# EEZ_DIB_AUX_PS_r3B5.net
KiCad netlist of a schematic drawn in EAGLE
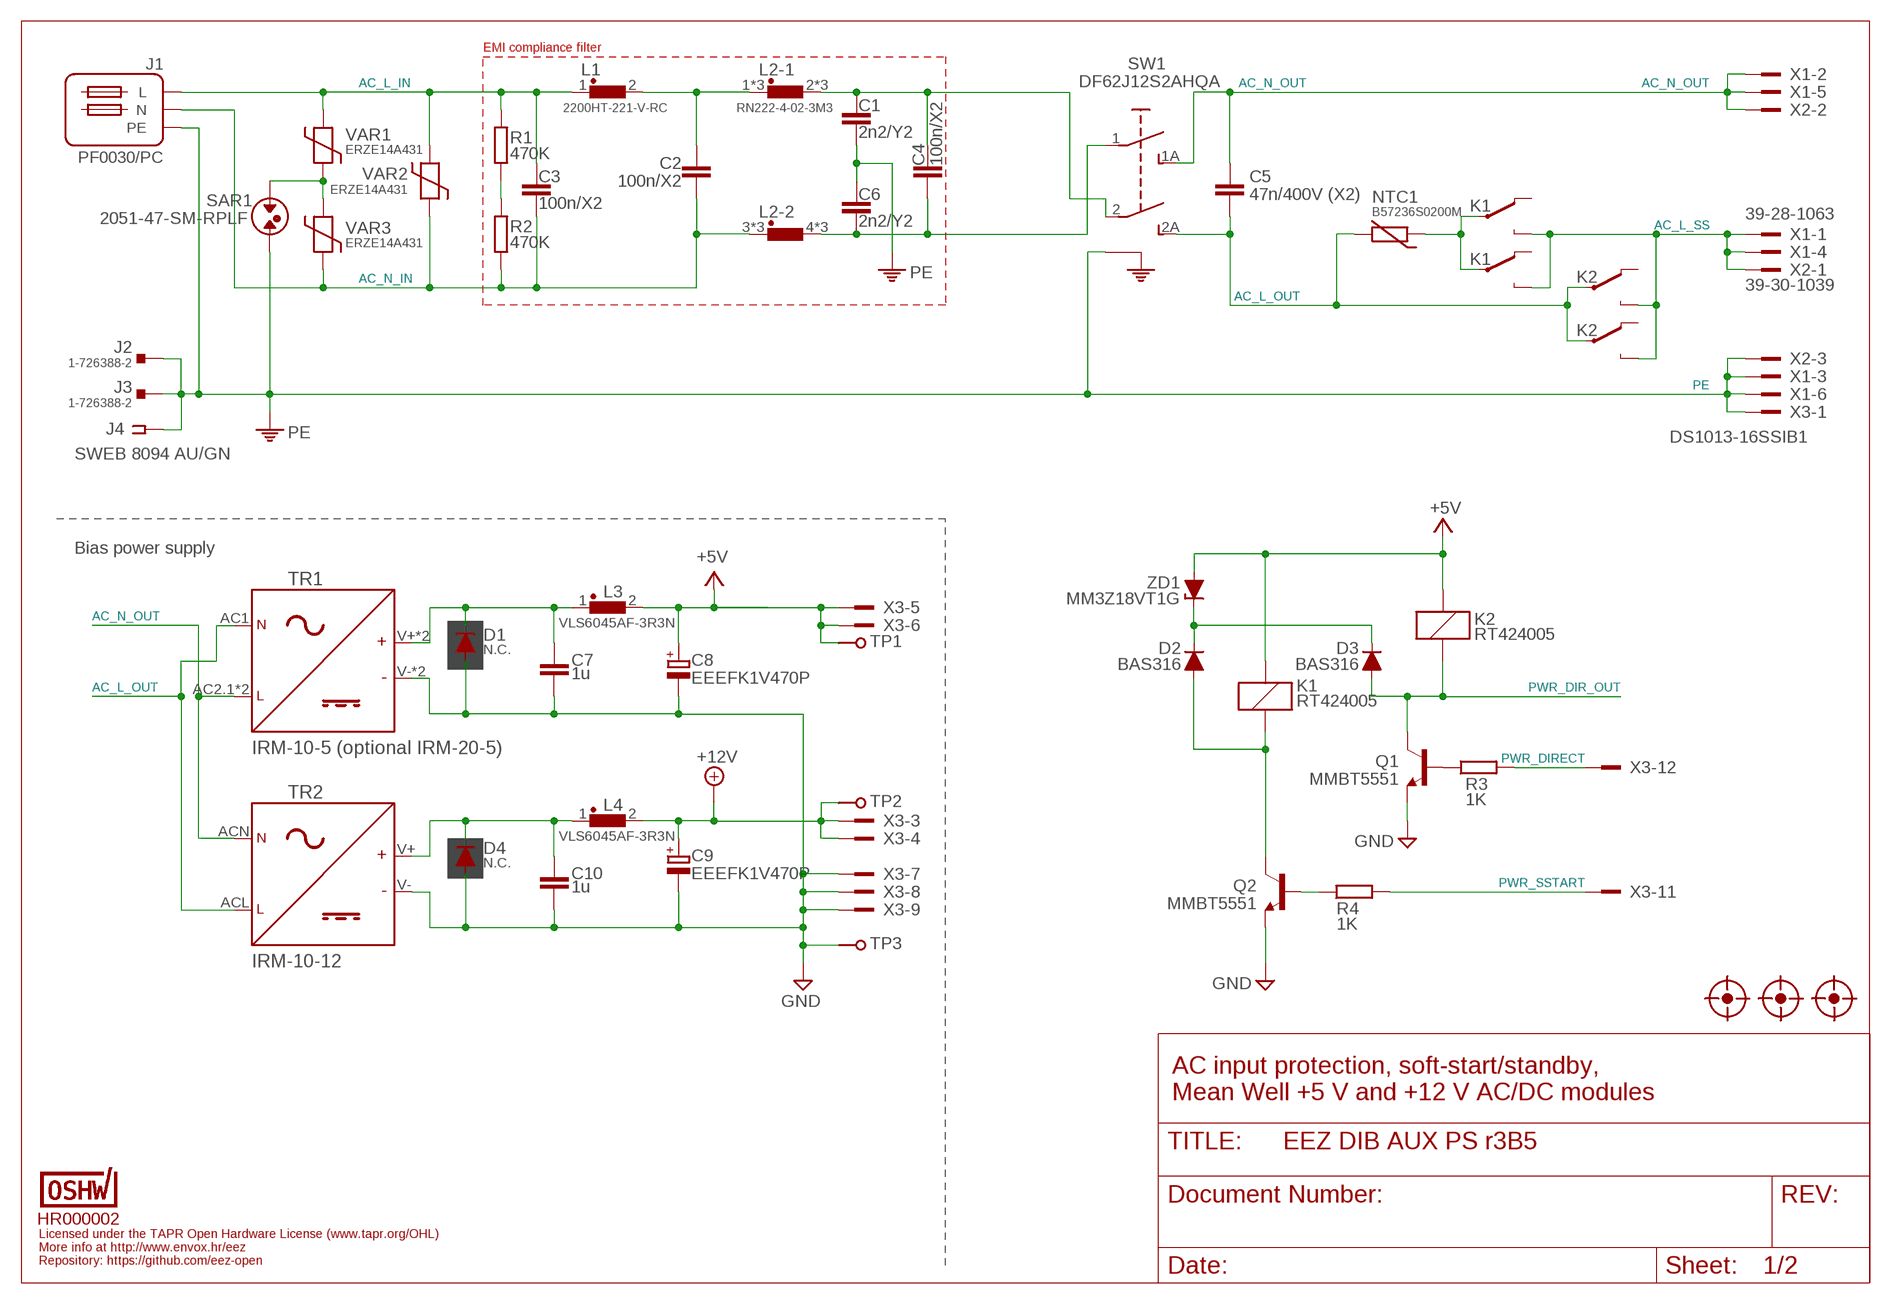
[diagram p0: schematic, sheet 1]
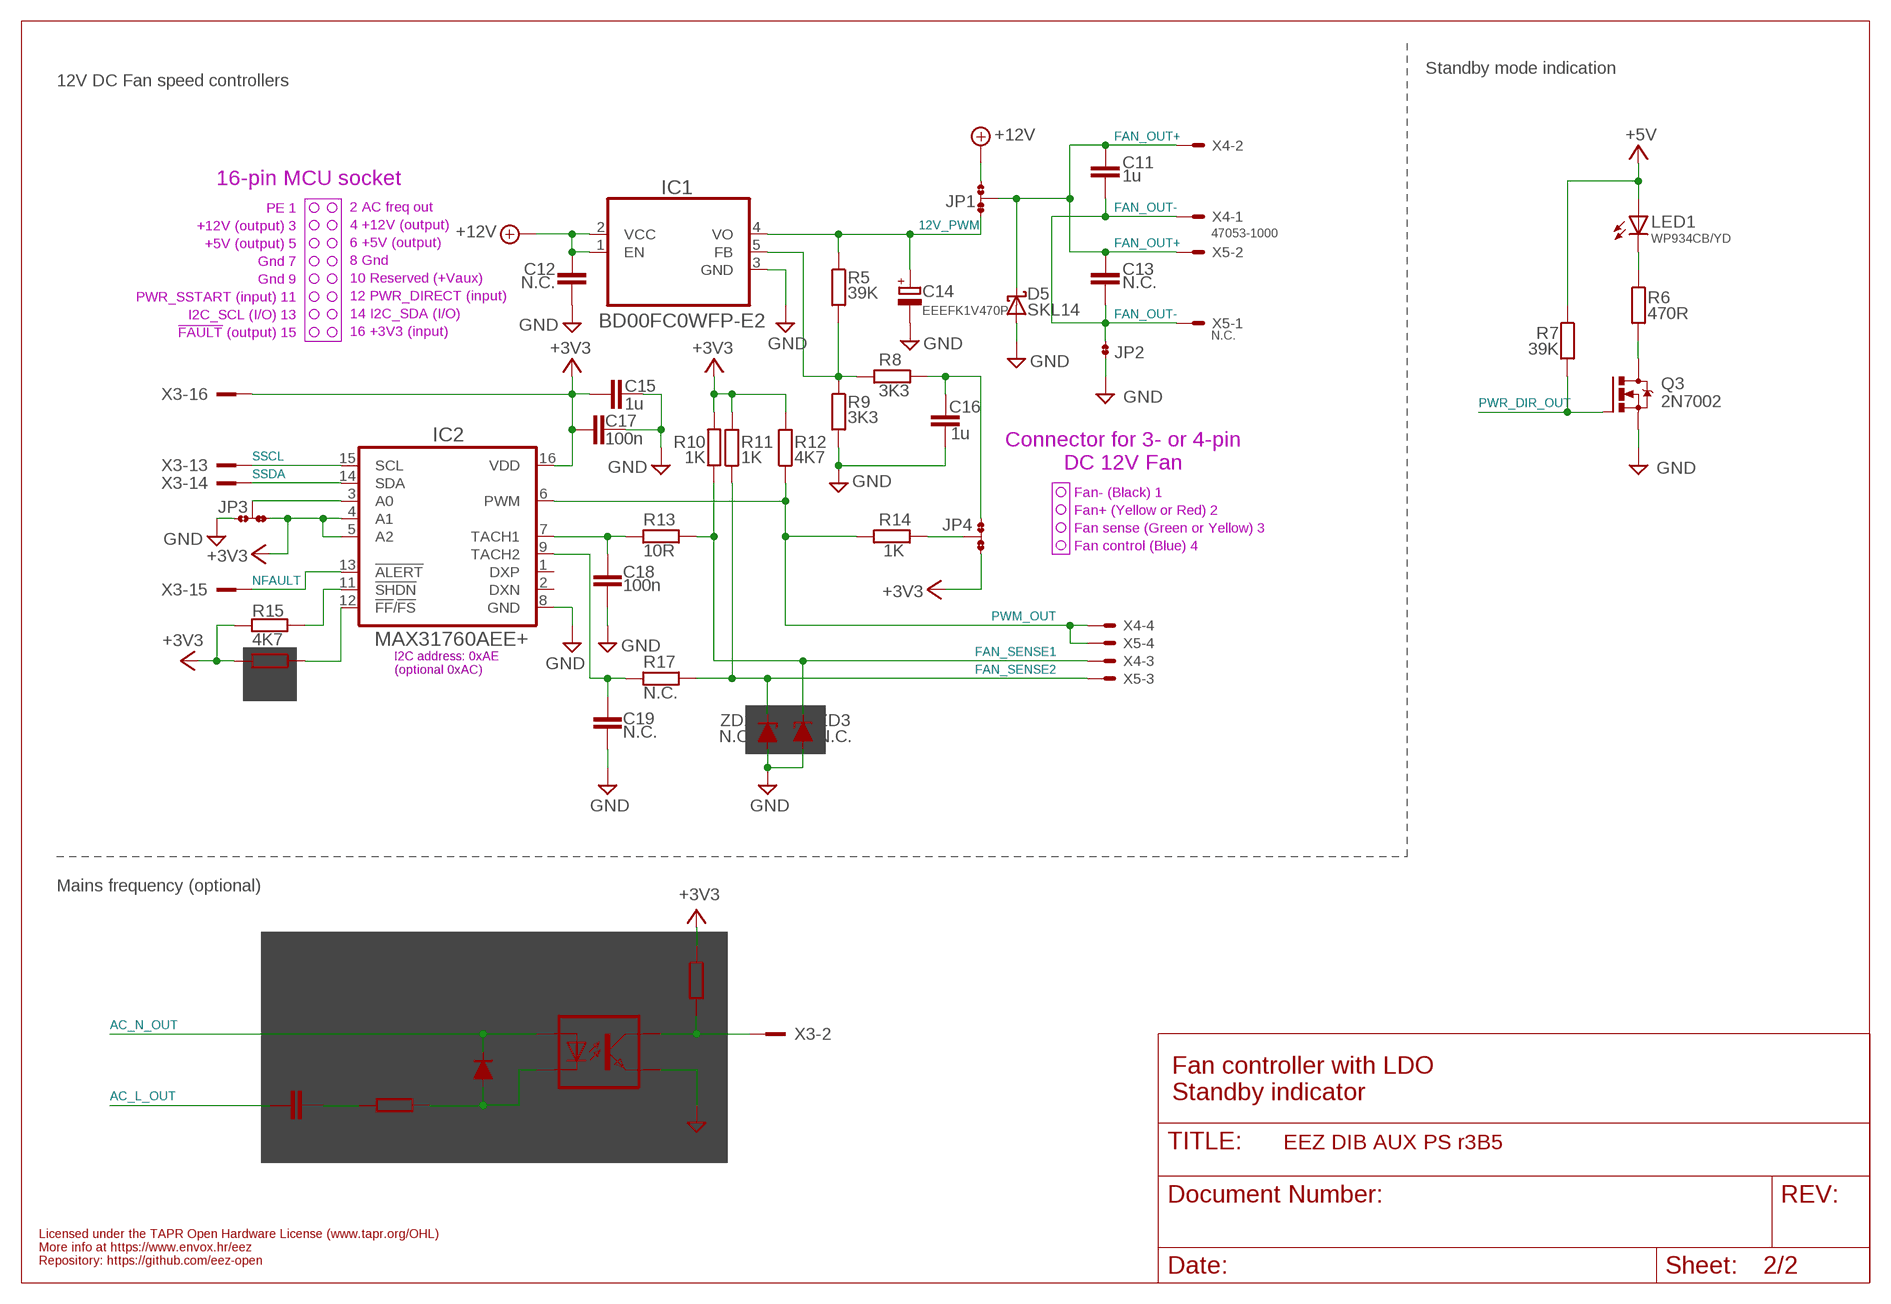
[diagram p1: schematic, sheet 2]

(export (version "E")
  (design (tool "Eeschema 10.0.6"))
  (components
    (comp (ref "C11")
      (value "1u")
      (footprint "eagle-import:C0805")
      (libsource (lib "eagle-import") (part "C-EUC0805"))
    )
    (comp (ref "C12")
      (value "N.C.")
      (footprint "eagle-import:C0805")
      (libsource (lib "eagle-import") (part "C-EUC0805"))
    )
    (comp (ref "C13")
      (value "N.C.")
      (footprint "eagle-import:C0805")
      (libsource (lib "eagle-import") (part "C-EUC0805"))
    )
    (comp (ref "C14")
      (value "EEEFK1V470P")
      (footprint "eagle-import:CAPAE660X610N")
      (libsource (lib "eagle-import") (part "ECAPPANASONIC_H"))
    )
    (comp (ref "C15")
      (value "1u")
      (footprint "eagle-import:C0805")
      (libsource (lib "eagle-import") (part "C-EUC0805"))
    )
    (comp (ref "C16")
      (value "1u")
      (footprint "eagle-import:C0805")
      (libsource (lib "eagle-import") (part "C-EUC0805"))
    )
    (comp (ref "C17")
      (value "100n")
      (footprint "eagle-import:C0603")
      (libsource (lib "eagle-import") (part "C-EUC0603"))
    )
    (comp (ref "C18")
      (value "100n")
      (footprint "eagle-import:C0603")
      (libsource (lib "eagle-import") (part "C-EUC0603"))
    )
    (comp (ref "C19")
      (value "N.C.")
      (footprint "eagle-import:C0603")
      (libsource (lib "eagle-import") (part "C-EUC0603"))
    )
    (comp (ref "C20")
      (value "N.C.")
      (footprint "eagle-import:C102-054X133")
      (libsource (lib "eagle-import") (part "C-EU102-054X133"))
    )
    (comp (ref "D5")
      (value "SKL14")
      (footprint "eagle-import:SOD123")
      (libsource (lib "eagle-import") (part "SCHOTTKYSOD123"))
    )
    (comp (ref "D6")
      (value "N.C.")
      (footprint "eagle-import:SOD323-R")
      (libsource (lib "eagle-import") (part "DIODESOD323R"))
    )
    (comp (ref "IC1")
      (value "BD00FC0WFP-E2")
      (footprint "eagle-import:TO-252-5")
      (libsource (lib "eagle-import") (part "BD00FC0W"))
    )
    (comp (ref "IC2")
      (value "MAX31760AEE+")
      (footprint "eagle-import:DBQ16")
      (libsource (lib "eagle-import") (part "MAX31760AEE+"))
    )
    (comp (ref "JP1")
      (value "JP3-CUT-0805-ROTATED")
      (footprint "eagle-import:JP3-0805-CUT2")
      (libsource (lib "eagle-import") (part "JP3-CUT-0805-ROTATED"))
    )
    (comp (ref "JP2")
      (value "JP2-NOCUT-0805")
      (footprint "eagle-import:JP2-0805-NOCUT")
      (libsource (lib "eagle-import") (part "JP2-NOCUT-0805"))
    )
    (comp (ref "JP3")
      (value "JP3-CUT-0805-ROTATED")
      (footprint "eagle-import:JP3-0805-CUT2")
      (libsource (lib "eagle-import") (part "JP3-CUT-0805-ROTATED"))
    )
    (comp (ref "JP4")
      (value "JP3-CUT-0805-ROTATED")
      (footprint "eagle-import:JP3-0805-CUT2")
      (libsource (lib "eagle-import") (part "JP3-CUT-0805-ROTATED"))
    )
    (comp (ref "LED1")
      (value "WP934CB/YD")
      (footprint "eagle-import:WP934CB_YD")
      (libsource (lib "eagle-import") (part "WP934CB/YD"))
    )
    (comp (ref "OK1")
      (value "N.C.")
      (footprint "eagle-import:SO4")
      (libsource (lib "eagle-import") (part "TLP291"))
    )
    (comp (ref "Q3")
      (value "2N7002")
      (footprint "eagle-import:SOT103P240X110-3N")
      (fields
        (field (name "MPN") "2N7002-7-F")
        (field (name "MPN_1") "2N7002-7-F")
        (field (name "OC_FARNELL") "1713823")
        (field (name "OC_NEWARK") "25R5679")
        (field (name "PACKAGE") "SOT-23-3")
        (field (name "SUPPLIER") "DIODES INC.")
      )
      (libsource (lib "eagle-import") (part "2N7002"))
    )
    (comp (ref "R5")
      (value "39K")
      (footprint "eagle-import:R0805")
      (libsource (lib "eagle-import") (part "R-EU_R0805"))
    )
    (comp (ref "R6")
      (value "470R")
      (footprint "eagle-import:R0805")
      (libsource (lib "eagle-import") (part "R-EU_R0805"))
    )
    (comp (ref "R7")
      (value "39K")
      (footprint "eagle-import:R0805")
      (libsource (lib "eagle-import") (part "R-EU_R0805"))
    )
    (comp (ref "R8")
      (value "3K3")
      (footprint "eagle-import:R0805")
      (libsource (lib "eagle-import") (part "R-EU_R0805"))
    )
    (comp (ref "R9")
      (value "3K3")
      (footprint "eagle-import:R0805")
      (libsource (lib "eagle-import") (part "R-EU_R0805"))
    )
    (comp (ref "R10")
      (value "1K")
      (footprint "eagle-import:R0805")
      (libsource (lib "eagle-import") (part "R-EU_R0805"))
    )
    (comp (ref "R11")
      (value "1K")
      (footprint "eagle-import:R0805")
      (libsource (lib "eagle-import") (part "R-EU_R0805"))
    )
    (comp (ref "R12")
      (value "4K7")
      (footprint "eagle-import:R0805")
      (libsource (lib "eagle-import") (part "R-EU_R0805"))
    )
    (comp (ref "R13")
      (value "10R")
      (footprint "eagle-import:R0805")
      (libsource (lib "eagle-import") (part "R-EU_R0805"))
    )
    (comp (ref "R14")
      (value "1K")
      (footprint "eagle-import:R0805")
      (libsource (lib "eagle-import") (part "R-EU_R0805"))
    )
    (comp (ref "R15")
      (value "4K7")
      (footprint "eagle-import:R0805")
      (libsource (lib "eagle-import") (part "R-EU_R0805"))
    )
    (comp (ref "R16")
      (value "N.C.")
      (footprint "eagle-import:R0805")
      (libsource (lib "eagle-import") (part "R-EU_R0805"))
    )
    (comp (ref "R17")
      (value "N.C.")
      (footprint "eagle-import:R0805")
      (libsource (lib "eagle-import") (part "R-EU_R0805"))
    )
    (comp (ref "R18")
      (value "N.C.")
      (footprint "eagle-import:R0805")
      (libsource (lib "eagle-import") (part "R-EU_R0805"))
    )
    (comp (ref "R19")
      (value "N.C.")
      (footprint "eagle-import:R0805")
      (libsource (lib "eagle-import") (part "R-EU_R0805"))
    )
    (comp (ref "X3")
      (value "DS1013-16SSIB1")
      (footprint "eagle-import:IDC-16PIN")
      (libsource (lib "eagle-import") (part "IDC-16PIN"))
    )
    (comp (ref "X4")
      (value "47053-1000")
      (footprint "eagle-import:47053-1000")
      (libsource (lib "eagle-import") (part "47053-1000"))
    )
    (comp (ref "X5")
      (value "N.C.")
      (footprint "eagle-import:47053-1000")
      (libsource (lib "eagle-import") (part "47053-1000"))
    )
    (comp (ref "ZD2")
      (value "N.C.")
      (footprint "eagle-import:SOD123")
      (libsource (lib "eagle-import") (part "ZENER-DIODESOD123"))
    )
    (comp (ref "ZD3")
      (value "N.C.")
      (footprint "eagle-import:SOD123")
      (libsource (lib "eagle-import") (part "ZENER-DIODESOD123"))
    )
    (comp (ref "C1")
      (value "2n2/Y2")
      (footprint "eagle-import:C075-042X103")
      (libsource (lib "eagle-import") (part "C-EU075-042X103"))
    )
    (comp (ref "C2")
      (value "100n/X2")
      (footprint "eagle-import:C150-054X183")
      (libsource (lib "eagle-import") (part "C-EU150-054X183"))
    )
    (comp (ref "C3")
      (value "100n/X2")
      (footprint "eagle-import:C150-054X183")
      (libsource (lib "eagle-import") (part "C-EU150-054X183"))
    )
    (comp (ref "C4")
      (value "100n/X2")
      (footprint "eagle-import:C150-054X183")
      (libsource (lib "eagle-import") (part "C-EU150-054X183"))
    )
    (comp (ref "C5")
      (value "47n/400V (X2)")
      (footprint "eagle-import:C102-054X133")
      (libsource (lib "eagle-import") (part "C-EU102-054X133"))
    )
    (comp (ref "C6")
      (value "2n2/Y2")
      (footprint "eagle-import:C075-042X103")
      (libsource (lib "eagle-import") (part "C-EU075-042X103"))
    )
    (comp (ref "C7")
      (value "1u")
      (footprint "eagle-import:C0805")
      (libsource (lib "eagle-import") (part "C-EUC0805"))
    )
    (comp (ref "C8")
      (value "EEEFK1V470P")
      (footprint "eagle-import:CAPAE660X610N")
      (libsource (lib "eagle-import") (part "ECAPPANASONIC_H"))
    )
    (comp (ref "C9")
      (value "EEEFK1V470P")
      (footprint "eagle-import:CAPAE660X610N")
      (libsource (lib "eagle-import") (part "ECAPPANASONIC_H"))
    )
    (comp (ref "C10")
      (value "1u")
      (footprint "eagle-import:C0805")
      (libsource (lib "eagle-import") (part "C-EUC0805"))
    )
    (comp (ref "D1")
      (value "N.C.")
      (footprint "eagle-import:DO214AA")
      (libsource (lib "eagle-import") (part "MyLib6_DIODEDO214AA"))
    )
    (comp (ref "D2")
      (value "BAS316")
      (footprint "eagle-import:SOD323-R")
      (libsource (lib "eagle-import") (part "DIODESOD323R"))
    )
    (comp (ref "D3")
      (value "BAS316")
      (footprint "eagle-import:SOD323-R")
      (libsource (lib "eagle-import") (part "DIODESOD323R"))
    )
    (comp (ref "D4")
      (value "N.C.")
      (footprint "eagle-import:DO214AA")
      (libsource (lib "eagle-import") (part "MyLib6_DIODEDO214AA"))
    )
    (comp (ref "FM1")
      (value "FIDUCIAL")
      (footprint "eagle-import:FIDUCIAL")
      (libsource (lib "eagle-import") (part "FIDUCIAL"))
    )
    (comp (ref "FM2")
      (value "FIDUCIAL")
      (footprint "eagle-import:FIDUCIAL")
      (libsource (lib "eagle-import") (part "FIDUCIAL"))
    )
    (comp (ref "FM3")
      (value "FIDUCIAL")
      (footprint "eagle-import:FIDUCIAL")
      (libsource (lib "eagle-import") (part "FIDUCIAL"))
    )
    (comp (ref "J1")
      (value "PF0030/PC")
      (footprint "eagle-import:PF0030_PC")
      (libsource (lib "eagle-import") (part "PF0030/PC"))
    )
    (comp (ref "J2")
      (value "1-726388-2")
      (footprint "eagle-import:PCB_TAB-4.8MM")
      (libsource (lib "eagle-import") (part "PCB_TAB4.8MM"))
    )
    (comp (ref "J3")
      (value "1-726388-2")
      (footprint "eagle-import:PCB_TAB-4.8MM")
      (libsource (lib "eagle-import") (part "PCB_TAB4.8MM"))
    )
    (comp (ref "J4")
      (value "SWEB 8094 AU/GN")
      (footprint "eagle-import:S16N-PC")
      (libsource (lib "eagle-import") (part "BINDING_POSTCLIFF"))
    )
    (comp (ref "K1")
      (value "RT424005")
      (footprint "eagle-import:RT-C_016A5_ROUND")
      (libsource (lib "eagle-import") (part "RELAY_RT314012-2"))
    )
    (comp (ref "K2")
      (value "RT424005")
      (footprint "eagle-import:RT-C_016A5_ROUND")
      (libsource (lib "eagle-import") (part "RELAY_RT314012-2"))
    )
    (comp (ref "L1")
      (value "2200HT-221-V-RC")
      (footprint "eagle-import:BOURNS_2200")
      (libsource (lib "eagle-import") (part "BOURNS_2200"))
    )
    (comp (ref "L2")
      (value "RN222-4-02-3M3")
      (footprint "eagle-import:BOURNS_7100_COMBO")
      (libsource (lib "eagle-import") (part "BOURNS_7100-COMBO"))
    )
    (comp (ref "L3")
      (value "VLS6045AF-3R3N")
      (footprint "eagle-import:COILCRAFT_HPI0630")
      (libsource (lib "eagle-import") (part "COILCRAFT_HPI0630"))
    )
    (comp (ref "L4")
      (value "VLS6045AF-3R3N")
      (footprint "eagle-import:COILCRAFT_HPI0630")
      (libsource (lib "eagle-import") (part "COILCRAFT_HPI0630"))
    )
    (comp (ref "LABEL1")
      (value "HR000002")
      (footprint "eagle-import:CERT-SMALL-SILK")
      (libsource (lib "eagle-import") (part "OSHWA-CERT-SMALL"))
    )
    (comp (ref "NTC1")
      (value "B57236S0200M")
      (footprint "eagle-import:NTC_11.5X6_RM5")
      (libsource (lib "eagle-import") (part "NTC11.5X6"))
    )
    (comp (ref "Q1")
      (value "MMBT5551")
      (footprint "eagle-import:SOT23-BEC")
      (libsource (lib "eagle-import") (part "-NPN-SOT23-BECMMBT5551LT1"))
    )
    (comp (ref "Q2")
      (value "MMBT5551")
      (footprint "eagle-import:SOT23-BEC")
      (libsource (lib "eagle-import") (part "-NPN-SOT23-BECMMBT5551LT1"))
    )
    (comp (ref "R1")
      (value "470K")
      (footprint "eagle-import:R1206")
      (libsource (lib "eagle-import") (part "R-EU_R1206"))
    )
    (comp (ref "R2")
      (value "470K")
      (footprint "eagle-import:R1206")
      (libsource (lib "eagle-import") (part "R-EU_R1206"))
    )
    (comp (ref "R3")
      (value "1K")
      (footprint "eagle-import:R0805")
      (libsource (lib "eagle-import") (part "R-EU_R0805"))
    )
    (comp (ref "R4")
      (value "1K")
      (footprint "eagle-import:R0805")
      (libsource (lib "eagle-import") (part "R-EU_R0805"))
    )
    (comp (ref "SAR1")
      (value "2051-47-SM-RPLF")
      (footprint "eagle-import:SAR_4.5MM")
      (libsource (lib "eagle-import") (part "SAR-SG"))
    )
    (comp (ref "SW1")
      (value "DF62J12S2AHQA")
      (footprint "eagle-import:DF62J12S2")
      (libsource (lib "eagle-import") (part "DF62J12S2AHQA"))
    )
    (comp (ref "TP1")
      (value "PCB_TEST_TABSHIELD")
      (footprint "eagle-import:PCB_SHIELD_TAB")
      (libsource (lib "eagle-import") (part "PCB_TEST_TABSHIELD"))
    )
    (comp (ref "TP2")
      (value "PCB_TEST_TABSHIELD")
      (footprint "eagle-import:PCB_SHIELD_TAB")
      (libsource (lib "eagle-import") (part "PCB_TEST_TABSHIELD"))
    )
    (comp (ref "TP3")
      (value "PCB_TEST_TABSHIELD")
      (footprint "eagle-import:PCB_SHIELD_TAB")
      (libsource (lib "eagle-import") (part "PCB_TEST_TABSHIELD"))
    )
    (comp (ref "TR1")
      (value "IRM-10-5 (optional IRM-20-5)")
      (footprint "eagle-import:IRM-10_20_COMBO")
      (libsource (lib "eagle-import") (part "AC_DC_ADAPTERIRM10/20"))
    )
    (comp (ref "TR2")
      (value "IRM-10-12")
      (footprint "eagle-import:IRM-10")
      (libsource (lib "eagle-import") (part "AC_DC_ADAPTERIRM10"))
    )
    (comp (ref "VAR1")
      (value "ERZE14A431")
      (footprint "eagle-import:VARISTOR_16MM")
      (libsource (lib "eagle-import") (part "VARISTOR-16"))
    )
    (comp (ref "VAR2")
      (value "ERZE14A431")
      (footprint "eagle-import:VARISTOR_16MM")
      (libsource (lib "eagle-import") (part "VARISTOR-16"))
    )
    (comp (ref "VAR3")
      (value "ERZE14A431")
      (footprint "eagle-import:VARISTOR_16MM")
      (libsource (lib "eagle-import") (part "VARISTOR-16"))
    )
    (comp (ref "X1")
      (value "39-28-1063")
      (footprint "eagle-import:MINIFIT_5566-06A_CRE")
      (libsource (lib "eagle-import") (part "MINIFIT_5566-06A-CRE"))
    )
    (comp (ref "X2")
      (value "39-30-1039")
      (footprint "eagle-import:MINIFIT_39301039_CRE")
      (libsource (lib "eagle-import") (part "MINIFIT_39301039-CREEPAGE"))
    )
    (comp (ref "ZD1")
      (value "MM3Z18VT1G")
      (footprint "eagle-import:SOD323-R")
      (libsource (lib "eagle-import") (part "ZENER-DIODESOD323R"))
    )
  )
  (nets
    (net (code "1") (name "+3V3") (class "Default")
      (node (ref "C15") (pin "2") (pinfunction "2_2") (pintype "passive"))
      (node (ref "C17") (pin "2") (pinfunction "2_2") (pintype "passive"))
      (node (ref "IC2") (pin "16") (pinfunction "VDD_16") (pintype "power_in"))
      (node (ref "IC2") (pin "4") (pinfunction "A1_4") (pintype "input"))
      (node (ref "IC2") (pin "5") (pinfunction "A2_5") (pintype "input"))
      (node (ref "JP3") (pin "NC") (pinfunction "NC_NC") (pintype "passive"))
      (node (ref "JP4") (pin "NO") (pinfunction "NO_NO") (pintype "passive"))
      (node (ref "R10") (pin "2") (pinfunction "2_2") (pintype "passive"))
      (node (ref "R11") (pin "2") (pinfunction "2_2") (pintype "passive"))
      (node (ref "R12") (pin "2") (pinfunction "2_2") (pintype "passive"))
      (node (ref "R15") (pin "2") (pinfunction "2_2") (pintype "passive"))
      (node (ref "R16") (pin "2") (pinfunction "2_2") (pintype "passive"))
      (node (ref "R18") (pin "1") (pinfunction "1_1") (pintype "passive"))
      (node (ref "X3") (pin "16") (pinfunction "1_16") (pintype "passive"))
    )
    (net (code "2") (name "+5V") (class "Default")
      (node (ref "C8") (pin "1") (pinfunction "+_1") (pintype "passive"))
      (node (ref "K1") (pin "A2") (pinfunction "C1_A2") (pintype "passive"))
      (node (ref "K2") (pin "A1") (pinfunction "C2_A1") (pintype "passive"))
      (node (ref "L3") (pin "2") (pinfunction "2_2") (pintype "passive"))
      (node (ref "LED1") (pin "A") (pinfunction "A_A") (pintype "passive"))
      (node (ref "R7") (pin "1") (pinfunction "1_1") (pintype "passive"))
      (node (ref "TP1") (pin "1") (pinfunction "P$1_1") (pintype "bidirectional"))
      (node (ref "X3") (pin "5") (pinfunction "1_5") (pintype "passive"))
      (node (ref "X3") (pin "6") (pinfunction "1_6") (pintype "passive"))
      (node (ref "ZD1") (pin "A") (pinfunction "A_A") (pintype "passive"))
    )
    (net (code "3") (name "+12V") (class "Default")
      (node (ref "C12") (pin "1") (pinfunction "1_1") (pintype "passive"))
      (node (ref "C9") (pin "1") (pinfunction "+_1") (pintype "passive"))
      (node (ref "IC1") (pin "1") (pinfunction "EN_1") (pintype "passive"))
      (node (ref "IC1") (pin "2") (pinfunction "VCC_2") (pintype "passive"))
      (node (ref "JP1") (pin "NO") (pinfunction "NO_NO") (pintype "passive"))
      (node (ref "L4") (pin "2") (pinfunction "2_2") (pintype "passive"))
      (node (ref "TP2") (pin "1") (pinfunction "P$1_1") (pintype "bidirectional"))
      (node (ref "X3") (pin "3") (pinfunction "1_3") (pintype "passive"))
      (node (ref "X3") (pin "4") (pinfunction "1_4") (pintype "passive"))
    )
    (net (code "4") (name "12V_PWM") (class "Default")
      (node (ref "C14") (pin "1") (pinfunction "+_1") (pintype "passive"))
      (node (ref "IC1") (pin "4") (pinfunction "VO_4") (pintype "output"))
      (node (ref "JP1") (pin "NC") (pinfunction "NC_NC") (pintype "passive"))
      (node (ref "R5") (pin "1") (pinfunction "1_1") (pintype "passive"))
    )
    (net (code "5") (name "AC_L_IN") (class "Default")
      (node (ref "C3") (pin "1") (pinfunction "1_1") (pintype "passive"))
      (node (ref "J1") (pin "L") (pinfunction "L_L") (pintype "bidirectional"))
      (node (ref "L1") (pin "1") (pinfunction "1_1") (pintype "passive"))
      (node (ref "R1") (pin "2") (pinfunction "2_2") (pintype "passive"))
      (node (ref "VAR1") (pin "2") (pinfunction "P$2_2") (pintype "bidirectional"))
      (node (ref "VAR2") (pin "1") (pinfunction "P$1_1") (pintype "bidirectional"))
    )
    (net (code "6") (name "AC_L_OUT") (class "Default")
      (node (ref "C20") (pin "1") (pinfunction "1_1") (pintype "passive"))
      (node (ref "C5") (pin "2") (pinfunction "2_2") (pintype "passive"))
      (node (ref "K2") (pin "11A") (pinfunction "P_11A") (pintype "passive"))
      (node (ref "K2") (pin "11B") (pinfunction "P_11B") (pintype "passive"))
      (node (ref "NTC1") (pin "1") (pinfunction "P$1_1") (pintype "bidirectional"))
      (node (ref "SW1") (pin "2A") (pinfunction "S1_2A") (pintype "passive"))
      (node (ref "TR1") (pin "AC1") (pinfunction "AC/N_AC1") (pintype "input"))
      (node (ref "TR2") (pin "ACL") (pinfunction "AC/L_ACL") (pintype "input"))
    )
    (net (code "7") (name "AC_L_SS") (class "Default")
      (node (ref "K1") (pin "14A") (pinfunction "O_14A") (pintype "passive"))
      (node (ref "K1") (pin "14B") (pinfunction "O_14B") (pintype "passive"))
      (node (ref "K2") (pin "14A") (pinfunction "O_14A") (pintype "passive"))
      (node (ref "K2") (pin "14B") (pinfunction "O_14B") (pintype "passive"))
      (node (ref "X1") (pin "1") (pinfunction "1_1") (pintype "passive"))
      (node (ref "X1") (pin "4") (pinfunction "1_4") (pintype "passive"))
      (node (ref "X2") (pin "1") (pinfunction "1_1") (pintype "passive"))
    )
    (net (code "8") (name "AC_N_IN") (class "Default")
      (node (ref "C2") (pin "2") (pinfunction "2_2") (pintype "passive"))
      (node (ref "C3") (pin "2") (pinfunction "2_2") (pintype "passive"))
      (node (ref "J1") (pin "N") (pinfunction "N_N") (pintype "bidirectional"))
      (node (ref "L2") (pin "3") (pinfunction "1_3") (pintype "passive"))
      (node (ref "L2") (pin "3A") (pinfunction "1_3A") (pintype "passive"))
      (node (ref "L2") (pin "3B") (pinfunction "1_3B") (pintype "passive"))
      (node (ref "R2") (pin "1") (pinfunction "1_1") (pintype "passive"))
      (node (ref "VAR2") (pin "2") (pinfunction "P$2_2") (pintype "bidirectional"))
      (node (ref "VAR3") (pin "1") (pinfunction "P$1_1") (pintype "bidirectional"))
    )
    (net (code "9") (name "AC_N_OUT") (class "Default")
      (node (ref "C5") (pin "1") (pinfunction "1_1") (pintype "passive"))
      (node (ref "D6") (pin "C") (pinfunction "C_C") (pintype "passive"))
      (node (ref "OK1") (pin "1") (pinfunction "A_1") (pintype "passive"))
      (node (ref "SW1") (pin "1A") (pinfunction "S_1A") (pintype "passive"))
      (node (ref "TR1") (pin "AC2.1") (pinfunction "AC/L_AC2.1") (pintype "input"))
      (node (ref "TR1") (pin "AC2.2") (pinfunction "AC/L_AC2.2") (pintype "input"))
      (node (ref "TR2") (pin "ACN") (pinfunction "AC/N_ACN") (pintype "input"))
      (node (ref "X1") (pin "2") (pinfunction "1_2") (pintype "passive"))
      (node (ref "X1") (pin "5") (pinfunction "1_5") (pintype "passive"))
      (node (ref "X2") (pin "2") (pinfunction "1_2") (pintype "passive"))
    )
    (net (code "10") (name "FAN_OUT+") (class "Default")
      (node (ref "C11") (pin "1") (pinfunction "1_1") (pintype "passive"))
      (node (ref "C13") (pin "1") (pinfunction "1_1") (pintype "passive"))
      (node (ref "D5") (pin "C") (pinfunction "C_C") (pintype "passive"))
      (node (ref "JP1") (pin "COM") (pinfunction "COM_COM") (pintype "passive"))
      (node (ref "X4") (pin "2") (pinfunction "S_2") (pintype "passive"))
      (node (ref "X5") (pin "2") (pinfunction "S_2") (pintype "passive"))
    )
    (net (code "11") (name "FAN_OUT-") (class "Default")
      (node (ref "C11") (pin "2") (pinfunction "2_2") (pintype "passive"))
      (node (ref "C13") (pin "2") (pinfunction "2_2") (pintype "passive"))
      (node (ref "JP2") (pin "2") (pinfunction "2_2") (pintype "passive"))
      (node (ref "X4") (pin "1") (pinfunction "S_1") (pintype "passive"))
      (node (ref "X5") (pin "1") (pinfunction "S_1") (pintype "passive"))
    )
    (net (code "12") (name "FAN_SENSE1") (class "Default")
      (node (ref "R10") (pin "1") (pinfunction "1_1") (pintype "passive"))
      (node (ref "R13") (pin "2") (pinfunction "2_2") (pintype "passive"))
      (node (ref "X4") (pin "3") (pinfunction "S_3") (pintype "passive"))
      (node (ref "ZD3") (pin "C") (pinfunction "C_C") (pintype "passive"))
    )
    (net (code "13") (name "FAN_SENSE2") (class "Default")
      (node (ref "R11") (pin "1") (pinfunction "1_1") (pintype "passive"))
      (node (ref "R17") (pin "2") (pinfunction "2_2") (pintype "passive"))
      (node (ref "X5") (pin "3") (pinfunction "S_3") (pintype "passive"))
      (node (ref "ZD2") (pin "C") (pinfunction "C_C") (pintype "passive"))
    )
    (net (code "14") (name "GND") (class "Default")
      (node (ref "C10") (pin "2") (pinfunction "2_2") (pintype "passive"))
      (node (ref "C12") (pin "2") (pinfunction "2_2") (pintype "passive"))
      (node (ref "C14") (pin "2") (pinfunction "-_2") (pintype "passive"))
      (node (ref "C15") (pin "1") (pinfunction "1_1") (pintype "passive"))
      (node (ref "C16") (pin "2") (pinfunction "2_2") (pintype "passive"))
      (node (ref "C17") (pin "1") (pinfunction "1_1") (pintype "passive"))
      (node (ref "C18") (pin "2") (pinfunction "2_2") (pintype "passive"))
      (node (ref "C19") (pin "2") (pinfunction "2_2") (pintype "passive"))
      (node (ref "C7") (pin "2") (pinfunction "2_2") (pintype "passive"))
      (node (ref "C8") (pin "2") (pinfunction "-_2") (pintype "passive"))
      (node (ref "C9") (pin "2") (pinfunction "-_2") (pintype "passive"))
      (node (ref "D1") (pin "A") (pinfunction "A_A") (pintype "passive"))
      (node (ref "D4") (pin "A") (pinfunction "A_A") (pintype "passive"))
      (node (ref "D5") (pin "A") (pinfunction "A_A") (pintype "passive"))
      (node (ref "IC1") (pin "3") (pinfunction "GND_3") (pintype "passive"))
      (node (ref "IC2") (pin "8") (pinfunction "GND_8") (pintype "power_in"))
      (node (ref "JP2") (pin "1") (pinfunction "1_1") (pintype "passive"))
      (node (ref "JP3") (pin "NO") (pinfunction "NO_NO") (pintype "passive"))
      (node (ref "OK1") (pin "3") (pinfunction "EMIT_3") (pintype "passive"))
      (node (ref "Q1") (pin "E") (pinfunction "E_E") (pintype "passive"))
      (node (ref "Q2") (pin "E") (pinfunction "E_E") (pintype "passive"))
      (node (ref "Q3") (pin "2") (pinfunction "S_2") (pintype "passive"))
      (node (ref "R9") (pin "2") (pinfunction "2_2") (pintype "passive"))
      (node (ref "TP3") (pin "1") (pinfunction "P$1_1") (pintype "bidirectional"))
      (node (ref "TR1") (pin "V-") (pinfunction "-_V-") (pintype "passive"))
      (node (ref "TR1") (pin "V-1") (pinfunction "-_V-1") (pintype "passive"))
      (node (ref "TR2") (pin "V-") (pinfunction "-_V-") (pintype "passive"))
      (node (ref "X3") (pin "7") (pinfunction "1_7") (pintype "passive"))
      (node (ref "X3") (pin "8") (pinfunction "1_8") (pintype "passive"))
      (node (ref "X3") (pin "9") (pinfunction "1_9") (pintype "passive"))
      (node (ref "ZD2") (pin "A") (pinfunction "A_A") (pintype "passive"))
      (node (ref "ZD3") (pin "A") (pinfunction "A_A") (pintype "passive"))
    )
    (net (code "15") (name "NFAULT") (class "Default")
      (node (ref "IC2") (pin "13") (pinfunction "~{ALERT}_13") (pintype "output"))
      (node (ref "X3") (pin "15") (pinfunction "1_15") (pintype "passive"))
    )
    (net (code "16") (name "Net-(C2-Pad1)") (class "Default")
      (node (ref "C2") (pin "1") (pinfunction "1_1") (pintype "passive"))
      (node (ref "L1") (pin "2") (pinfunction "2_2") (pintype "passive"))
      (node (ref "L2") (pin "1") (pinfunction "1_1") (pintype "passive"))
      (node (ref "L2") (pin "1A") (pinfunction "1_1A") (pintype "passive"))
      (node (ref "L2") (pin "1B") (pinfunction "1_1B") (pintype "passive"))
    )
    (net (code "17") (name "Net-(C7-Pad1)") (class "Default")
      (node (ref "C7") (pin "1") (pinfunction "1_1") (pintype "passive"))
      (node (ref "D1") (pin "C") (pinfunction "C_C") (pintype "passive"))
      (node (ref "L3") (pin "1") (pinfunction "1_1") (pintype "passive"))
      (node (ref "TR1") (pin "V+") (pinfunction "+_V+") (pintype "passive"))
      (node (ref "TR1") (pin "V+1") (pinfunction "+_V+1") (pintype "passive"))
    )
    (net (code "18") (name "Net-(C16-Pad1)") (class "Default")
      (node (ref "C16") (pin "1") (pinfunction "1_1") (pintype "passive"))
      (node (ref "JP4") (pin "NC") (pinfunction "NC_NC") (pintype "passive"))
      (node (ref "R8") (pin "2") (pinfunction "2_2") (pintype "passive"))
    )
    (net (code "19") (name "Net-(C20-Pad2)") (class "Default")
      (node (ref "C20") (pin "2") (pinfunction "2_2") (pintype "passive"))
      (node (ref "R19") (pin "1") (pinfunction "1_1") (pintype "passive"))
    )
    (net (code "20") (name "Net-(D2-PadC)") (class "Default")
      (node (ref "D2") (pin "C") (pinfunction "C_C") (pintype "passive"))
      (node (ref "D3") (pin "C") (pinfunction "C_C") (pintype "passive"))
      (node (ref "ZD1") (pin "C") (pinfunction "C_C") (pintype "passive"))
    )
    (net (code "21") (name "Net-(IC1-FB)") (class "Default")
      (node (ref "IC1") (pin "5") (pinfunction "FB_5") (pintype "passive"))
      (node (ref "R5") (pin "2") (pinfunction "2_2") (pintype "passive"))
      (node (ref "R8") (pin "1") (pinfunction "1_1") (pintype "passive"))
      (node (ref "R9") (pin "1") (pinfunction "1_1") (pintype "passive"))
    )
    (net (code "22") (name "Net-(IC2-A0)") (class "Default")
      (node (ref "IC2") (pin "3") (pinfunction "A0_3") (pintype "input"))
      (node (ref "JP3") (pin "COM") (pinfunction "COM_COM") (pintype "passive"))
    )
    (net (code "23") (name "Net-(IC2-TACH1)") (class "Default")
      (node (ref "C18") (pin "1") (pinfunction "1_1") (pintype "passive"))
      (node (ref "IC2") (pin "7") (pinfunction "TACH1_7") (pintype "input"))
      (node (ref "R13") (pin "1") (pinfunction "1_1") (pintype "passive"))
    )
    (net (code "24") (name "Net-(IC2-TACH2)") (class "Default")
      (node (ref "C19") (pin "1") (pinfunction "1_1") (pintype "passive"))
      (node (ref "IC2") (pin "9") (pinfunction "TACH2_9") (pintype "input"))
      (node (ref "R17") (pin "1") (pinfunction "1_1") (pintype "passive"))
    )
    (net (code "25") (name "Net-(IC2-~{FF}{slash}~{FS})") (class "Default")
      (node (ref "IC2") (pin "12") (pinfunction "~{FF}/~{FS}_12") (pintype "bidirectional"))
      (node (ref "R16") (pin "1") (pinfunction "1_1") (pintype "passive"))
    )
    (net (code "26") (name "Net-(IC2-~{SHDN})") (class "Default")
      (node (ref "IC2") (pin "11") (pinfunction "~{SHDN}_11") (pintype "output"))
      (node (ref "R15") (pin "1") (pinfunction "1_1") (pintype "passive"))
    )
    (net (code "27") (name "Net-(JP4-PadCOM)") (class "Default")
      (node (ref "JP4") (pin "COM") (pinfunction "COM_COM") (pintype "passive"))
      (node (ref "R14") (pin "1") (pinfunction "1_1") (pintype "passive"))
    )
    (net (code "28") (name "Net-(K1A-P)") (class "Default")
      (node (ref "K1") (pin "11A") (pinfunction "P_11A") (pintype "passive"))
      (node (ref "K1") (pin "11B") (pinfunction "P_11B") (pintype "passive"))
      (node (ref "NTC1") (pin "2") (pinfunction "P$2_2") (pintype "bidirectional"))
    )
    (net (code "29") (name "Net-(K1C-C2)") (class "Default")
      (node (ref "D2") (pin "A") (pinfunction "A_A") (pintype "passive"))
      (node (ref "K1") (pin "A1") (pinfunction "C2_A1") (pintype "passive"))
      (node (ref "Q2") (pin "C") (pinfunction "C_C") (pintype "passive"))
    )
    (net (code "30") (name "Net-(LED1-PadC)") (class "Default")
      (node (ref "LED1") (pin "C") (pinfunction "C_C") (pintype "passive"))
      (node (ref "R6") (pin "1") (pinfunction "1_1") (pintype "passive"))
    )
    (net (code "31") (name "Net-(OK1-C)") (class "Default")
      (node (ref "D6") (pin "A") (pinfunction "A_A") (pintype "passive"))
      (node (ref "OK1") (pin "2") (pinfunction "C_2") (pintype "passive"))
      (node (ref "R19") (pin "2") (pinfunction "2_2") (pintype "passive"))
    )
    (net (code "32") (name "Net-(OK1-COL)") (class "Default")
      (node (ref "OK1") (pin "4") (pinfunction "COL_4") (pintype "passive"))
      (node (ref "R18") (pin "2") (pinfunction "2_2") (pintype "passive"))
      (node (ref "X3") (pin "2") (pinfunction "1_2") (pintype "passive"))
    )
    (net (code "33") (name "Net-(Q1-PadB)") (class "Default")
      (node (ref "Q1") (pin "B") (pinfunction "B_B") (pintype "passive"))
      (node (ref "R3") (pin "1") (pinfunction "1_1") (pintype "passive"))
    )
    (net (code "34") (name "Net-(Q2-PadB)") (class "Default")
      (node (ref "Q2") (pin "B") (pinfunction "B_B") (pintype "passive"))
      (node (ref "R4") (pin "1") (pinfunction "1_1") (pintype "passive"))
    )
    (net (code "35") (name "Net-(Q3-D)") (class "Default")
      (node (ref "Q3") (pin "3") (pinfunction "D_3") (pintype "passive"))
      (node (ref "R6") (pin "2") (pinfunction "2_2") (pintype "passive"))
    )
    (net (code "36") (name "Net-(R1-Pad1)") (class "Default")
      (node (ref "R1") (pin "1") (pinfunction "1_1") (pintype "passive"))
      (node (ref "R2") (pin "2") (pinfunction "2_2") (pintype "passive"))
    )
    (net (code "37") (name "Net-(SAR1-P$1)") (class "Default")
      (node (ref "SAR1") (pin "1") (pinfunction "P$1_1") (pintype "bidirectional"))
      (node (ref "VAR1") (pin "1") (pinfunction "P$1_1") (pintype "bidirectional"))
      (node (ref "VAR3") (pin "2") (pinfunction "P$2_2") (pintype "bidirectional"))
    )
    (net (code "38") (name "Net-(SW1-P)") (class "Default")
      (node (ref "C4") (pin "1") (pinfunction "1_1") (pintype "passive"))
      (node (ref "C6") (pin "2") (pinfunction "2_2") (pintype "passive"))
      (node (ref "L2") (pin "4") (pinfunction "2_4") (pintype "passive"))
      (node (ref "L2") (pin "4A") (pinfunction "2_4A") (pintype "passive"))
      (node (ref "L2") (pin "4B") (pinfunction "2_4B") (pintype "passive"))
      (node (ref "SW1") (pin "1") (pinfunction "P_1") (pintype "passive"))
    )
    (net (code "39") (name "Net-(SW1-P1)") (class "Default")
      (node (ref "C1") (pin "1") (pinfunction "1_1") (pintype "passive"))
      (node (ref "C4") (pin "2") (pinfunction "2_2") (pintype "passive"))
      (node (ref "L2") (pin "2") (pinfunction "2_2") (pintype "passive"))
      (node (ref "L2") (pin "2A") (pinfunction "2_2A") (pintype "passive"))
      (node (ref "L2") (pin "2B") (pinfunction "2_2B") (pintype "passive"))
      (node (ref "SW1") (pin "2") (pinfunction "P1_2") (pintype "passive"))
    )
    (net (code "40") (name "Net-(TR2-+)") (class "Default")
      (node (ref "C10") (pin "1") (pinfunction "1_1") (pintype "passive"))
      (node (ref "D4") (pin "C") (pinfunction "C_C") (pintype "passive"))
      (node (ref "L4") (pin "1") (pinfunction "1_1") (pintype "passive"))
      (node (ref "TR2") (pin "V+") (pinfunction "+_V+") (pintype "passive"))
    )
    (net (code "41") (name "PE") (class "Default")
      (node (ref "C1") (pin "2") (pinfunction "2_2") (pintype "passive"))
      (node (ref "C6") (pin "1") (pinfunction "1_1") (pintype "passive"))
      (node (ref "J1") (pin "PE") (pinfunction "PE_PE") (pintype "bidirectional"))
      (node (ref "J2") (pin "1") (pinfunction "P$1_1") (pintype "bidirectional"))
      (node (ref "J2") (pin "2") (pinfunction "P$1_2") (pintype "bidirectional"))
      (node (ref "J3") (pin "1") (pinfunction "P$1_1") (pintype "bidirectional"))
      (node (ref "J3") (pin "2") (pinfunction "P$1_2") (pintype "bidirectional"))
      (node (ref "J4") (pin "1") (pinfunction "1_1") (pintype "passive"))
      (node (ref "J4") (pin "NC1") (pinfunction "1_NC1") (pintype "passive"))
      (node (ref "J4") (pin "NC2") (pinfunction "1_NC2") (pintype "passive"))
      (node (ref "J4") (pin "NC3") (pinfunction "1_NC3") (pintype "passive"))
      (node (ref "J4") (pin "NC4") (pinfunction "1_NC4") (pintype "passive"))
      (node (ref "SAR1") (pin "2") (pinfunction "P$2_2") (pintype "bidirectional"))
      (node (ref "SW1") (pin "PE1") (pinfunction "PE_PE1") (pintype "power_in"))
      (node (ref "SW1") (pin "PE2") (pinfunction "PE_PE2") (pintype "power_in"))
      (node (ref "X1") (pin "3") (pinfunction "1_3") (pintype "passive"))
      (node (ref "X1") (pin "6") (pinfunction "1_6") (pintype "passive"))
      (node (ref "X2") (pin "3") (pinfunction "1_3") (pintype "passive"))
      (node (ref "X3") (pin "1") (pinfunction "1_1") (pintype "passive"))
    )
    (net (code "42") (name "PWM_OUT") (class "Default")
      (node (ref "IC2") (pin "6") (pinfunction "PWM_6") (pintype "output"))
      (node (ref "R12") (pin "1") (pinfunction "1_1") (pintype "passive"))
      (node (ref "R14") (pin "2") (pinfunction "2_2") (pintype "passive"))
      (node (ref "X4") (pin "4") (pinfunction "S_4") (pintype "passive"))
      (node (ref "X5") (pin "4") (pinfunction "S_4") (pintype "passive"))
    )
    (net (code "43") (name "PWR_DIRECT") (class "Default")
      (node (ref "R3") (pin "2") (pinfunction "2_2") (pintype "passive"))
      (node (ref "X3") (pin "12") (pinfunction "1_12") (pintype "passive"))
    )
    (net (code "44") (name "PWR_DIR_OUT") (class "Default")
      (node (ref "D3") (pin "A") (pinfunction "A_A") (pintype "passive"))
      (node (ref "K2") (pin "A2") (pinfunction "C1_A2") (pintype "passive"))
      (node (ref "Q1") (pin "C") (pinfunction "C_C") (pintype "passive"))
      (node (ref "Q3") (pin "1") (pinfunction "G_1") (pintype "passive"))
      (node (ref "R7") (pin "2") (pinfunction "2_2") (pintype "passive"))
    )
    (net (code "45") (name "PWR_SSTART") (class "Default")
      (node (ref "R4") (pin "2") (pinfunction "2_2") (pintype "passive"))
      (node (ref "X3") (pin "11") (pinfunction "1_11") (pintype "passive"))
    )
    (net (code "46") (name "SSCL") (class "Default")
      (node (ref "IC2") (pin "15") (pinfunction "SCL_15") (pintype "input"))
      (node (ref "X3") (pin "13") (pinfunction "1_13") (pintype "passive"))
    )
    (net (code "47") (name "SSDA") (class "Default")
      (node (ref "IC2") (pin "14") (pinfunction "SDA_14") (pintype "bidirectional"))
      (node (ref "X3") (pin "14") (pinfunction "1_14") (pintype "passive"))
    )
    (net (code "48") (name "unconnected-(IC2-DXN-Pad2)") (class "Default")
      (node (ref "IC2") (pin "2") (pinfunction "DXN_2") (pintype "input"))
    )
    (net (code "49") (name "unconnected-(IC2-DXP-Pad1)") (class "Default")
      (node (ref "IC2") (pin "1") (pinfunction "DXP_1") (pintype "input"))
    )
    (net (code "50") (name "unconnected-(K1A-S-Pad12A)") (class "Default")
      (node (ref "K1") (pin "12A") (pinfunction "S_12A") (pintype "passive"))
    )
    (net (code "51") (name "unconnected-(K1B-S-Pad12B)") (class "Default")
      (node (ref "K1") (pin "12B") (pinfunction "S_12B") (pintype "passive"))
    )
    (net (code "52") (name "unconnected-(K2A-S-Pad12A)") (class "Default")
      (node (ref "K2") (pin "12A") (pinfunction "S_12A") (pintype "passive"))
    )
    (net (code "53") (name "unconnected-(K2B-S-Pad12B)") (class "Default")
      (node (ref "K2") (pin "12B") (pinfunction "S_12B") (pintype "passive"))
    )
  )
)
